# IPA-Safety-Relay-Schematic.net
KiCad netlist of a schematic drawn in Altium Designer
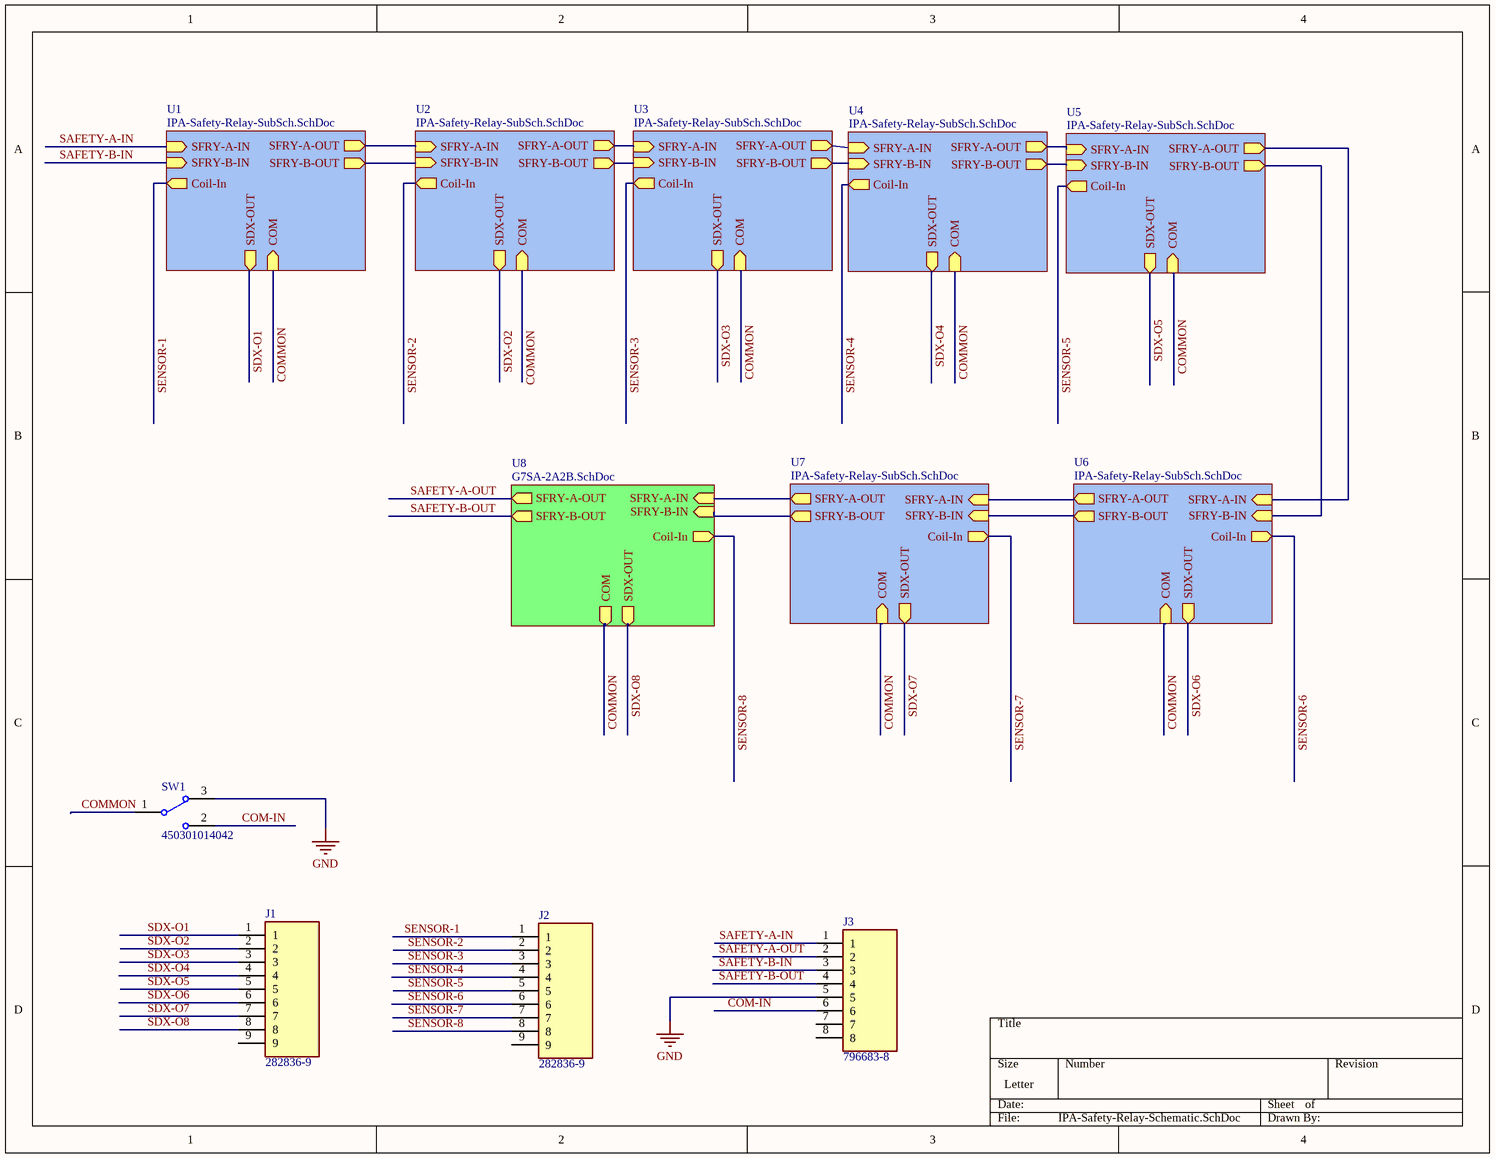
[diagram p0: IPA-Safety-Relay-Schematic.SchDoc]

(export (version "E")
  (design (tool "Eeschema 10.0.6"))
  (components
    (comp (ref "J1")
      (value "282836-9")
      (footprint "SamacSys:SHDR9W130P0X500_1X9_4500X820X1020P")
      (description "Connector")
      (fields (field (name "MOUSER PART NUMBER") "571-282836-9") (field (name "RS PART NUMBER") "3617746"))
      (libsource (lib "*") (part "282836-9"))
    )
    (comp (ref "J2")
      (value "282836-9")
      (footprint "SamacSys:SHDR9W130P0X500_1X9_4500X820X1020P")
      (description "Connector")
      (fields (field (name "MOUSER PART NUMBER") "571-282836-9") (field (name "RS PART NUMBER") "3617746"))
      (libsource (lib "*") (part "282836-9"))
    )
    (comp (ref "J3")
      (value "796683-8")
      (footprint "SamacSys:SHDR8W110P0X500_1X8_4000X900X1520P")
      (description "Connector")
      (fields (field (name "MOUSER PART NUMBER") "571-796683-8"))
      (libsource (lib "*") (part "796683-8"))
    )
    (comp (ref "SW1")
      (value "450301014042")
      (footprint "450301014042")
      (description "WS-SLTV 10mm*2.5mm, SPDT, ON-ON, 2.54mm, straight type, THT, Mini Slide Switch, 3 pins")
      (fields (field (name "MANUFACTURER") "Wuerth Elektronik"))
      (libsource (lib "Altium Content Vault") (part "WE-SLIDE-SW-3"))
    )
  )
  (nets
    (net (code "1") (name "/COM-IN") (class "Default")
      (node (ref "J3") (pin "6") (pinfunction "6_6") (pintype "passive"))
      (node (ref "SW1") (pin "2") (pinfunction "2_2") (pintype "passive"))
    )
    (net (code "2") (name "/COMMON") (class "Default")
      (node (ref "SW1") (pin "1") (pinfunction "1_1") (pintype "passive"))
    )
    (net (code "3") (name "/SAFETY-A-IN") (class "Default")
      (node (ref "J3") (pin "1") (pinfunction "1_1") (pintype "passive"))
    )
    (net (code "4") (name "/SAFETY-A-OUT") (class "Default")
      (node (ref "J3") (pin "2") (pinfunction "2_2") (pintype "passive"))
    )
    (net (code "5") (name "/SAFETY-B-IN") (class "Default")
      (node (ref "J3") (pin "3") (pinfunction "3_3") (pintype "passive"))
    )
    (net (code "6") (name "/SAFETY-B-OUT") (class "Default")
      (node (ref "J3") (pin "4") (pinfunction "4_4") (pintype "passive"))
    )
    (net (code "7") (name "/SDX-O1") (class "Default")
      (node (ref "J1") (pin "1") (pinfunction "1_1") (pintype "passive"))
    )
    (net (code "8") (name "/SDX-O2") (class "Default")
      (node (ref "J1") (pin "2") (pinfunction "2_2") (pintype "passive"))
    )
    (net (code "9") (name "/SDX-O3") (class "Default")
      (node (ref "J1") (pin "3") (pinfunction "3_3") (pintype "passive"))
    )
    (net (code "10") (name "/SDX-O4") (class "Default")
      (node (ref "J1") (pin "4") (pinfunction "4_4") (pintype "passive"))
    )
    (net (code "11") (name "/SDX-O5") (class "Default")
      (node (ref "J1") (pin "5") (pinfunction "5_5") (pintype "passive"))
    )
    (net (code "12") (name "/SDX-O6") (class "Default")
      (node (ref "J1") (pin "6") (pinfunction "6_6") (pintype "passive"))
    )
    (net (code "13") (name "/SDX-O7") (class "Default")
      (node (ref "J1") (pin "7") (pinfunction "7_7") (pintype "passive"))
    )
    (net (code "14") (name "/SDX-O8") (class "Default")
      (node (ref "J1") (pin "8") (pinfunction "8_8") (pintype "passive"))
    )
    (net (code "15") (name "/SENSOR-1") (class "Default")
      (node (ref "J2") (pin "1") (pinfunction "1_1") (pintype "passive"))
    )
    (net (code "16") (name "/SENSOR-2") (class "Default")
      (node (ref "J2") (pin "2") (pinfunction "2_2") (pintype "passive"))
    )
    (net (code "17") (name "/SENSOR-3") (class "Default")
      (node (ref "J2") (pin "3") (pinfunction "3_3") (pintype "passive"))
    )
    (net (code "18") (name "/SENSOR-4") (class "Default")
      (node (ref "J2") (pin "4") (pinfunction "4_4") (pintype "passive"))
    )
    (net (code "19") (name "/SENSOR-5") (class "Default")
      (node (ref "J2") (pin "5") (pinfunction "5_5") (pintype "passive"))
    )
    (net (code "20") (name "/SENSOR-6") (class "Default")
      (node (ref "J2") (pin "6") (pinfunction "6_6") (pintype "passive"))
    )
    (net (code "21") (name "/SENSOR-7") (class "Default")
      (node (ref "J2") (pin "7") (pinfunction "7_7") (pintype "passive"))
    )
    (net (code "22") (name "/SENSOR-8") (class "Default")
      (node (ref "J2") (pin "8") (pinfunction "8_8") (pintype "passive"))
    )
    (net (code "37") (name "GND") (class "Default")
      (node (ref "J3") (pin "5") (pinfunction "5_5") (pintype "passive"))
      (node (ref "SW1") (pin "3") (pinfunction "3_3") (pintype "passive"))
    )
    (net (code "38") (name "unconnected-(J1-Pad9)") (class "Default")
      (node (ref "J1") (pin "9") (pinfunction "9_9") (pintype "passive"))
    )
    (net (code "39") (name "unconnected-(J2-Pad9)") (class "Default")
      (node (ref "J2") (pin "9") (pinfunction "9_9") (pintype "passive"))
    )
    (net (code "40") (name "unconnected-(J3-Pad7)") (class "Default")
      (node (ref "J3") (pin "7") (pinfunction "7_7") (pintype "passive"))
    )
    (net (code "41") (name "unconnected-(J3-Pad8)") (class "Default")
      (node (ref "J3") (pin "8") (pinfunction "8_8") (pintype "passive"))
    )
  )
)
